# Input.net
KiCad netlist of a schematic drawn in Altium Designer
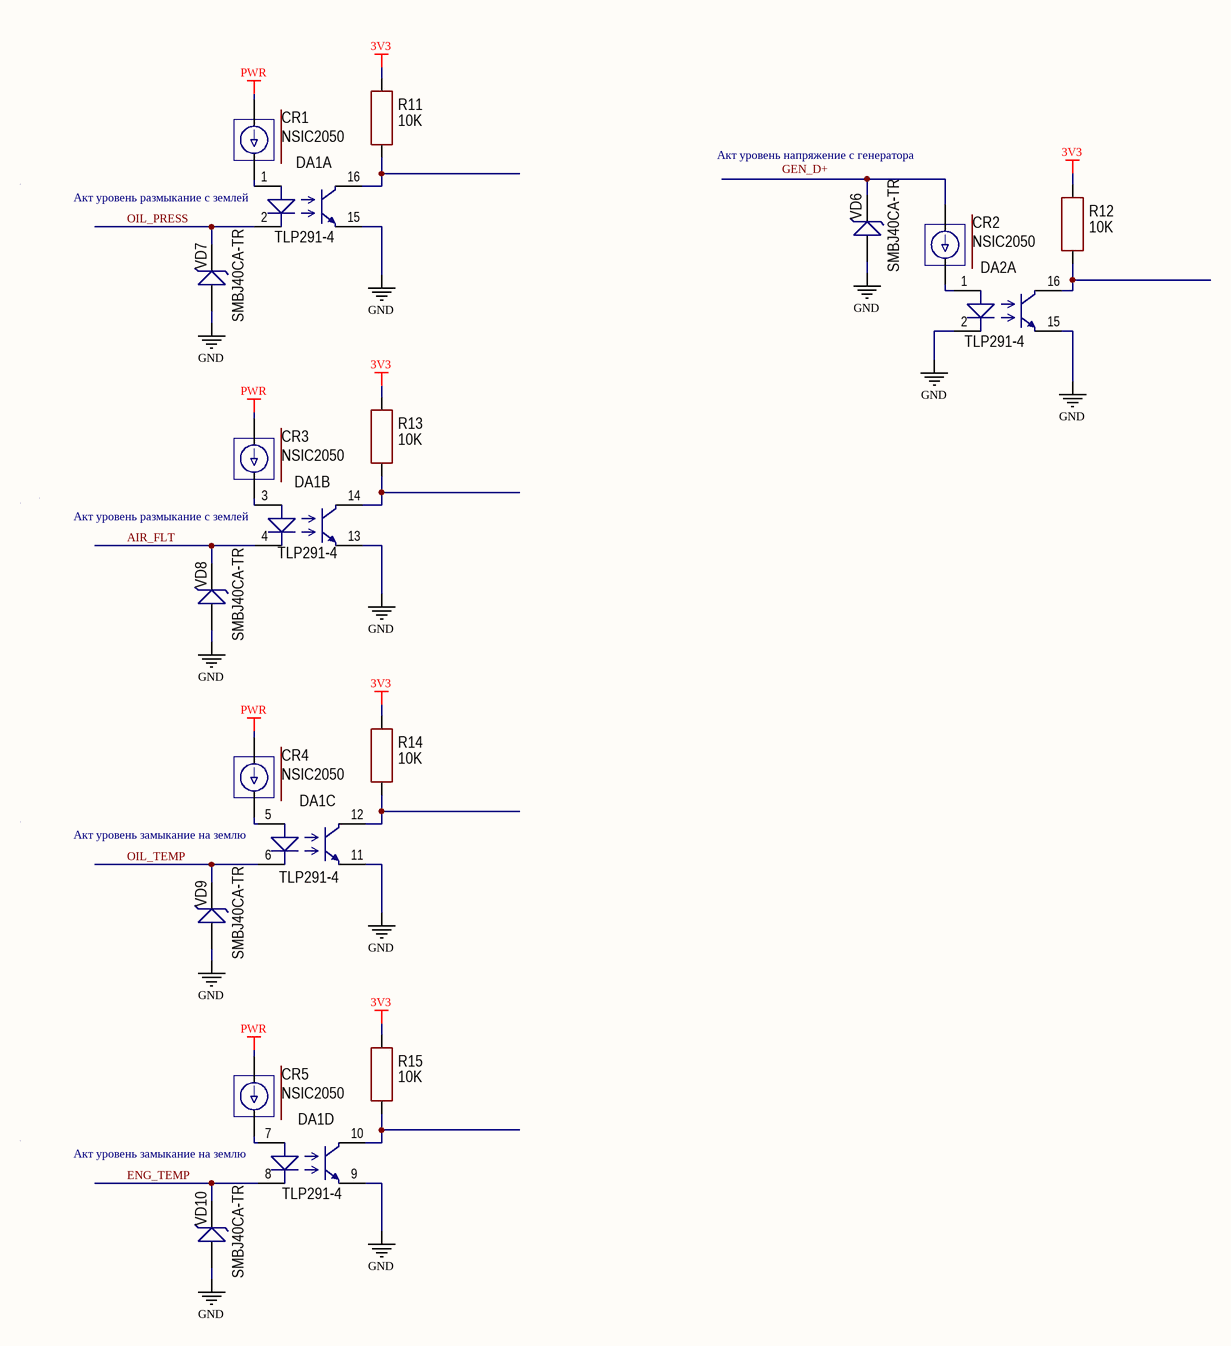
[diagram p0: Input.SchDoc]

(export (version "E")
  (design (tool "Eeschema 10.0.6"))
  (components
    (comp (ref "CR1")
      (value "NSIC2050")
      (footprint "SMB1")
      (fields (field (name "Comment") "NSIC20XX"))
      (libsource (lib "my_library") (part "NSIC20XX"))
    )
    (comp (ref "CR2")
      (value "NSIC2050")
      (footprint "SMB1")
      (fields (field (name "Comment") "NSIC20XX"))
      (libsource (lib "my_library") (part "NSIC20XX"))
    )
    (comp (ref "CR3")
      (value "NSIC2050")
      (footprint "SMB1")
      (fields (field (name "Comment") "NSIC20XX"))
      (libsource (lib "my_library") (part "NSIC20XX"))
    )
    (comp (ref "CR4")
      (value "NSIC2050")
      (footprint "SMB1")
      (fields (field (name "Comment") "NSIC20XX"))
      (libsource (lib "my_library") (part "NSIC20XX"))
    )
    (comp (ref "CR5")
      (value "NSIC2050")
      (footprint "SMB1")
      (fields (field (name "Comment") "NSIC20XX"))
      (libsource (lib "my_library") (part "NSIC20XX"))
    )
    (comp (ref "DA1") (value "TLP291-4") (footprint "SOP16") (libsource (lib "my_library") (part "TLP291-4")))
    (comp (ref "DA2") (value "TLP291-4") (footprint "SOP16") (libsource (lib "my_library") (part "TLP291-4")))
    (comp (ref "R11")
      (value "10K")
      (footprint "RES: 1206")
      (fields
        (field (name "MANUFACTURER") "Yageo")
        (field (name "PARTNUMBER") "RC1206JR-07100RL")
        (field (name "VALUEMANUFACTURERPARTNUMBER") "Resistor film, 10K, ±5%, 1206, 0.25W, -55...+125°C")
      )
      (libsource (lib "resistor") (part "Resistor_1206"))
    )
    (comp (ref "R12")
      (value "10K")
      (footprint "RES: 1206")
      (fields
        (field (name "MANUFACTURER") "Yageo")
        (field (name "PARTNUMBER") "RC1206JR-07100RL")
        (field (name "VALUEMANUFACTURERPARTNUMBER") "Resistor film, 10K, ±5%, 1206, 0.25W, -55...+125°C")
      )
      (libsource (lib "resistor") (part "Resistor_1206"))
    )
    (comp (ref "R13")
      (value "10K")
      (footprint "RES: 1206")
      (fields
        (field (name "MANUFACTURER") "Yageo")
        (field (name "PARTNUMBER") "RC1206JR-07100RL")
        (field (name "VALUEMANUFACTURERPARTNUMBER") "Resistor film, 10K, ±5%, 1206, 0.25W, -55...+125°C")
      )
      (libsource (lib "resistor") (part "Resistor_1206"))
    )
    (comp (ref "R14")
      (value "10K")
      (footprint "RES: 1206")
      (fields
        (field (name "MANUFACTURER") "Yageo")
        (field (name "PARTNUMBER") "RC1206JR-07100RL")
        (field (name "VALUEMANUFACTURERPARTNUMBER") "Resistor film, 10K, ±5%, 1206, 0.25W, -55...+125°C")
      )
      (libsource (lib "resistor") (part "Resistor_1206"))
    )
    (comp (ref "R15")
      (value "10K")
      (footprint "RES: 1206")
      (fields
        (field (name "MANUFACTURER") "Yageo")
        (field (name "PARTNUMBER") "RC1206JR-07100RL")
        (field (name "VALUEMANUFACTURERPARTNUMBER") "Resistor film, 10K, ±5%, 1206, 0.25W, -55...+125°C")
      )
      (libsource (lib "resistor") (part "Resistor_1206"))
    )
    (comp (ref "VD6")
      (value "SMBJ40CA-TR")
      (footprint "SMB")
      (fields (field (name "Comment") "suppressor"))
      (libsource (lib "my_library") (part "suppressor"))
    )
    (comp (ref "VD7")
      (value "SMBJ40CA-TR")
      (footprint "SMB")
      (fields (field (name "Comment") "suppressor"))
      (libsource (lib "my_library") (part "suppressor"))
    )
    (comp (ref "VD8")
      (value "SMBJ40CA-TR")
      (footprint "SMB")
      (fields (field (name "Comment") "suppressor"))
      (libsource (lib "my_library") (part "suppressor"))
    )
    (comp (ref "VD9")
      (value "SMBJ40CA-TR")
      (footprint "SMB")
      (fields (field (name "Comment") "suppressor"))
      (libsource (lib "my_library") (part "suppressor"))
    )
    (comp (ref "VD10")
      (value "SMBJ40CA-TR")
      (footprint "SMB")
      (fields (field (name "Comment") "suppressor"))
      (libsource (lib "my_library") (part "suppressor"))
    )
  )
  (nets
    (net (code "1") (name "/AIR_FLT") (class "Default")
      (node (ref "DA1") (pin "4") (pinfunction "4_4") (pintype "passive"))
      (node (ref "VD8") (pin "1") (pinfunction "1_1") (pintype "passive"))
    )
    (net (code "2") (name "/ENG_TEMP") (class "Default")
      (node (ref "DA1") (pin "8") (pinfunction "8_8") (pintype "passive"))
      (node (ref "VD10") (pin "1") (pinfunction "1_1") (pintype "passive"))
    )
    (net (code "4") (name "/OIL_PRESS") (class "Default")
      (node (ref "DA1") (pin "2") (pinfunction "2_2") (pintype "passive"))
      (node (ref "VD7") (pin "1") (pinfunction "1_1") (pintype "passive"))
    )
    (net (code "5") (name "/OIL_TEMP") (class "Default")
      (node (ref "DA1") (pin "6") (pinfunction "6_6") (pintype "passive"))
      (node (ref "VD9") (pin "1") (pinfunction "1_1") (pintype "passive"))
    )
    (net (code "6") (name "3V3") (class "Default")
      (node (ref "R11") (pin "2") (pinfunction "2_2") (pintype "passive"))
      (node (ref "R12") (pin "2") (pinfunction "2_2") (pintype "passive"))
      (node (ref "R13") (pin "2") (pinfunction "2_2") (pintype "passive"))
      (node (ref "R14") (pin "2") (pinfunction "2_2") (pintype "passive"))
      (node (ref "R15") (pin "2") (pinfunction "2_2") (pintype "passive"))
    )
    (net (code "7") (name "GND") (class "Default")
      (node (ref "DA1") (pin "11") (pinfunction "11_11") (pintype "passive"))
      (node (ref "DA1") (pin "13") (pinfunction "13_13") (pintype "passive"))
      (node (ref "DA1") (pin "15") (pinfunction "15_15") (pintype "passive"))
      (node (ref "DA1") (pin "9") (pinfunction "9_9") (pintype "passive"))
      (node (ref "DA2") (pin "15") (pinfunction "15_15") (pintype "passive"))
      (node (ref "DA2") (pin "2") (pinfunction "2_2") (pintype "passive"))
      (node (ref "VD10") (pin "2") (pinfunction "2_2") (pintype "passive"))
      (node (ref "VD6") (pin "2") (pinfunction "2_2") (pintype "passive"))
      (node (ref "VD7") (pin "2") (pinfunction "2_2") (pintype "passive"))
      (node (ref "VD8") (pin "2") (pinfunction "2_2") (pintype "passive"))
      (node (ref "VD9") (pin "2") (pinfunction "2_2") (pintype "passive"))
    )
    (net (code "8") (name "Net-(CR1-PadK)") (class "Default")
      (node (ref "CR1") (pin "K") (pinfunction "K_K") (pintype "passive"))
      (node (ref "DA1") (pin "1") (pinfunction "1_1") (pintype "passive"))
    )
    (net (code "9") (name "Net-(CR2-PadA)") (class "Default")
      (node (ref "CR2") (pin "A") (pinfunction "A_A") (pintype "passive"))
      (node (ref "VD6") (pin "1") (pinfunction "1_1") (pintype "passive"))
    )
    (net (code "10") (name "Net-(CR2-PadK)") (class "Default")
      (node (ref "CR2") (pin "K") (pinfunction "K_K") (pintype "passive"))
      (node (ref "DA2") (pin "1") (pinfunction "1_1") (pintype "passive"))
    )
    (net (code "11") (name "Net-(CR3-PadK)") (class "Default")
      (node (ref "CR3") (pin "K") (pinfunction "K_K") (pintype "passive"))
      (node (ref "DA1") (pin "3") (pinfunction "3_3") (pintype "passive"))
    )
    (net (code "12") (name "Net-(CR4-PadK)") (class "Default")
      (node (ref "CR4") (pin "K") (pinfunction "K_K") (pintype "passive"))
      (node (ref "DA1") (pin "5") (pinfunction "5_5") (pintype "passive"))
    )
    (net (code "13") (name "Net-(CR5-PadK)") (class "Default")
      (node (ref "CR5") (pin "K") (pinfunction "K_K") (pintype "passive"))
      (node (ref "DA1") (pin "7") (pinfunction "7_7") (pintype "passive"))
    )
    (net (code "14") (name "Net-(DA1-Pad10)") (class "Default")
      (node (ref "DA1") (pin "10") (pinfunction "10_10") (pintype "passive"))
      (node (ref "R15") (pin "1") (pinfunction "1_1") (pintype "passive"))
    )
    (net (code "15") (name "Net-(DA1-Pad12)") (class "Default")
      (node (ref "DA1") (pin "12") (pinfunction "12_12") (pintype "passive"))
      (node (ref "R14") (pin "1") (pinfunction "1_1") (pintype "passive"))
    )
    (net (code "16") (name "Net-(DA1-Pad14)") (class "Default")
      (node (ref "DA1") (pin "14") (pinfunction "14_14") (pintype "passive"))
      (node (ref "R13") (pin "1") (pinfunction "1_1") (pintype "passive"))
    )
    (net (code "17") (name "Net-(DA1-Pad16)") (class "Default")
      (node (ref "DA1") (pin "16") (pinfunction "16_16") (pintype "passive"))
      (node (ref "R11") (pin "1") (pinfunction "1_1") (pintype "passive"))
    )
    (net (code "18") (name "Net-(DA2-Pad16)") (class "Default")
      (node (ref "DA2") (pin "16") (pinfunction "16_16") (pintype "passive"))
      (node (ref "R12") (pin "1") (pinfunction "1_1") (pintype "passive"))
    )
    (net (code "19") (name "PWR") (class "Default")
      (node (ref "CR1") (pin "A") (pinfunction "A_A") (pintype "passive"))
      (node (ref "CR3") (pin "A") (pinfunction "A_A") (pintype "passive"))
      (node (ref "CR4") (pin "A") (pinfunction "A_A") (pintype "passive"))
      (node (ref "CR5") (pin "A") (pinfunction "A_A") (pintype "passive"))
    )
  )
)
